# DIY-Arduino-v0_1.net
KiCad netlist of a schematic drawn in EAGLE
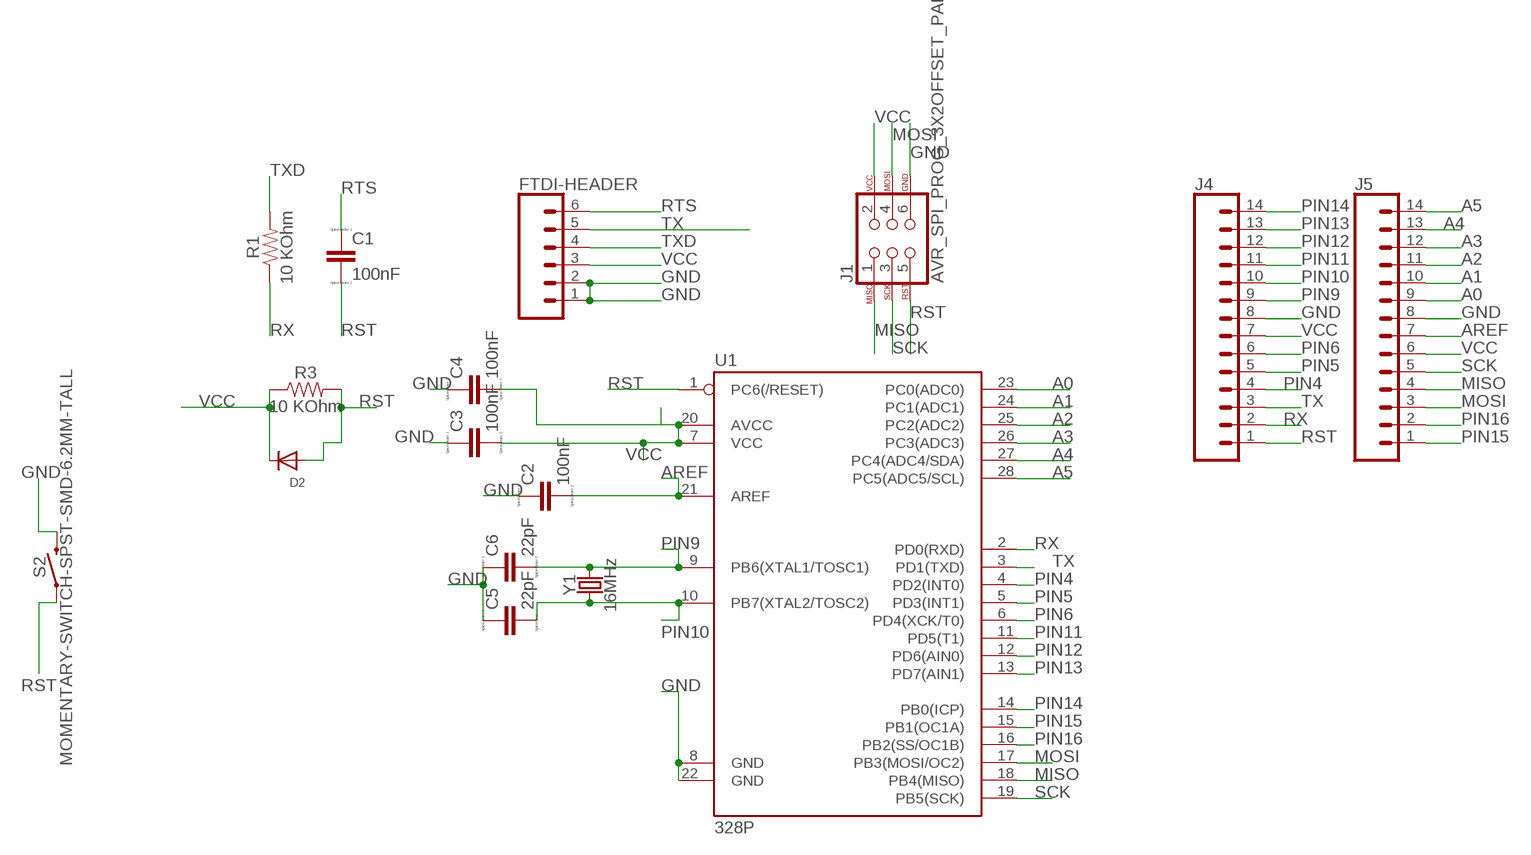
[diagram p0: schematic, sheet 1]

(export (version "E")
  (design (tool "Eeschema 10.0.6"))
  (components
    (comp (ref "C1")
      (value "100nF")
      (footprint "eagle-import:C1206")
      (libsource (lib "eagle-import") (part "CC1206"))
    )
    (comp (ref "C2")
      (value "100nF")
      (footprint "eagle-import:C1206")
      (libsource (lib "eagle-import") (part "CC1206"))
    )
    (comp (ref "C3")
      (value "100nF")
      (footprint "eagle-import:C1206")
      (libsource (lib "eagle-import") (part "CC1206"))
    )
    (comp (ref "C4")
      (value "100nF")
      (footprint "eagle-import:C1206")
      (libsource (lib "eagle-import") (part "CC1206"))
    )
    (comp (ref "C5")
      (value "22pF")
      (footprint "eagle-import:C1206")
      (libsource (lib "eagle-import") (part "CC1206"))
    )
    (comp (ref "C6")
      (value "22pF")
      (footprint "eagle-import:C1206")
      (libsource (lib "eagle-import") (part "CC1206"))
    )
    (comp (ref "D2")
      (value "DIODEDO-1N4148")
      (footprint "eagle-import:DO-1N4148")
      (libsource (lib "eagle-import") (part "DIODEDO-1N4148"))
    )
    (comp (ref "FTDI-HEADER")
      (value "CONN_06NO_SILK_FEMALE_PTH")
      (footprint "eagle-import:1X06_NO_SILK")
      (libsource (lib "eagle-import") (part "CONN_06NO_SILK_FEMALE_PTH"))
    )
    (comp (ref "J1")
      (value "AVR_SPI_PROG_3X2OFFSET_PADS")
      (footprint "eagle-import:2X3_OFFSET")
      (libsource (lib "eagle-import") (part "AVR_SPI_PROG_3X2OFFSET_PADS"))
    )
    (comp (ref "J4")
      (value "CONN_14NO_SILK")
      (footprint "eagle-import:1X14_NO_SILK")
      (libsource (lib "eagle-import") (part "CONN_14NO_SILK"))
    )
    (comp (ref "J5")
      (value "CONN_14NO_SILK")
      (footprint "eagle-import:1X14_NO_SILK")
      (libsource (lib "eagle-import") (part "CONN_14NO_SILK"))
    )
    (comp (ref "R1")
      (value "10 KOhm")
      (footprint "eagle-import:1206")
      (libsource (lib "eagle-import") (part "RESISTOR1206"))
    )
    (comp (ref "R3")
      (value "10 KOhm")
      (footprint "eagle-import:1206")
      (libsource (lib "eagle-import") (part "RESISTOR1206"))
    )
    (comp (ref "S2")
      (value "MOMENTARY-SWITCH-SPST-SMD-6.2MM-TALL")
      (footprint "eagle-import:TACTILE_SWITCH_SMD_6.2MM_TALL")
      (libsource (lib "eagle-import") (part "MOMENTARY-SWITCH-SPST-SMD-6.2MM-TALL"))
    )
    (comp (ref "U1")
      (value "328P")
      (footprint "eagle-import:DIP28")
      (libsource (lib "eagle-import") (part "ATMEGA328P_PDIP"))
    )
    (comp (ref "Y1")
      (value "16MHz")
      (footprint "eagle-import:HC49US")
      (libsource (lib "eagle-import") (part "CRYSTAL-16MHZPTH-HC49US"))
    )
  )
  (nets
    (net (code "1") (name "/A0") (class "Default")
      (node (ref "J5") (pin "9") (pinfunction "9_9") (pintype "passive"))
      (node (ref "U1") (pin "23") (pinfunction "PC0(ADC0)_23") (pintype "bidirectional"))
    )
    (net (code "2") (name "/A1") (class "Default")
      (node (ref "J5") (pin "10") (pinfunction "10_10") (pintype "passive"))
      (node (ref "U1") (pin "24") (pinfunction "PC1(ADC1)_24") (pintype "bidirectional"))
    )
    (net (code "3") (name "/A2") (class "Default")
      (node (ref "J5") (pin "11") (pinfunction "11_11") (pintype "passive"))
      (node (ref "U1") (pin "25") (pinfunction "PC2(ADC2)_25") (pintype "bidirectional"))
    )
    (net (code "4") (name "/A3") (class "Default")
      (node (ref "J5") (pin "12") (pinfunction "12_12") (pintype "passive"))
      (node (ref "U1") (pin "26") (pinfunction "PC3(ADC3)_26") (pintype "bidirectional"))
    )
    (net (code "5") (name "/A4") (class "Default")
      (node (ref "J5") (pin "13") (pinfunction "13_13") (pintype "passive"))
      (node (ref "U1") (pin "27") (pinfunction "PC4(ADC4/SDA)_27") (pintype "bidirectional"))
    )
    (net (code "6") (name "/A5") (class "Default")
      (node (ref "J5") (pin "14") (pinfunction "14_14") (pintype "passive"))
      (node (ref "U1") (pin "28") (pinfunction "PC5(ADC5/SCL)_28") (pintype "bidirectional"))
    )
    (net (code "7") (name "/AREF") (class "Default")
      (node (ref "C2") (pin "2") (pinfunction "2_2") (pintype "passive"))
      (node (ref "J5") (pin "7") (pinfunction "7_7") (pintype "passive"))
      (node (ref "U1") (pin "21") (pinfunction "AREF_21") (pintype "bidirectional"))
    )
    (net (code "8") (name "/GND") (class "Default")
      (node (ref "C2") (pin "1") (pinfunction "1_1") (pintype "passive"))
      (node (ref "C3") (pin "1") (pinfunction "1_1") (pintype "passive"))
      (node (ref "C4") (pin "1") (pinfunction "1_1") (pintype "passive"))
      (node (ref "C5") (pin "1") (pinfunction "1_1") (pintype "passive"))
      (node (ref "C6") (pin "1") (pinfunction "1_1") (pintype "passive"))
      (node (ref "FTDI-HEADER") (pin "1") (pinfunction "1_1") (pintype "passive"))
      (node (ref "FTDI-HEADER") (pin "2") (pinfunction "2_2") (pintype "passive"))
      (node (ref "J1") (pin "6") (pinfunction "6_6") (pintype "passive"))
      (node (ref "J4") (pin "8") (pinfunction "8_8") (pintype "passive"))
      (node (ref "J5") (pin "8") (pinfunction "8_8") (pintype "passive"))
      (node (ref "S2") (pin "B2") (pinfunction "2_B2") (pintype "passive"))
      (node (ref "U1") (pin "22") (pinfunction "GND_22") (pintype "bidirectional"))
      (node (ref "U1") (pin "8") (pinfunction "GND_8") (pintype "bidirectional"))
    )
    (net (code "9") (name "/MISO") (class "Default")
      (node (ref "J1") (pin "1") (pinfunction "1_1") (pintype "passive"))
      (node (ref "J5") (pin "4") (pinfunction "4_4") (pintype "passive"))
      (node (ref "U1") (pin "18") (pinfunction "PB4(MISO)_18") (pintype "bidirectional"))
    )
    (net (code "10") (name "/MOSI") (class "Default")
      (node (ref "J1") (pin "4") (pinfunction "4_4") (pintype "passive"))
      (node (ref "J5") (pin "3") (pinfunction "3_3") (pintype "passive"))
      (node (ref "U1") (pin "17") (pinfunction "PB3(MOSI/OC2)_17") (pintype "bidirectional"))
    )
    (net (code "11") (name "/PIN4") (class "Default")
      (node (ref "J4") (pin "4") (pinfunction "4_4") (pintype "passive"))
      (node (ref "U1") (pin "4") (pinfunction "PD2(INT0)_4") (pintype "bidirectional"))
    )
    (net (code "12") (name "/PIN5") (class "Default")
      (node (ref "J4") (pin "5") (pinfunction "5_5") (pintype "passive"))
      (node (ref "U1") (pin "5") (pinfunction "PD3(INT1)_5") (pintype "bidirectional"))
    )
    (net (code "13") (name "/PIN6") (class "Default")
      (node (ref "J4") (pin "6") (pinfunction "6_6") (pintype "passive"))
      (node (ref "U1") (pin "6") (pinfunction "PD4(XCK/T0)_6") (pintype "bidirectional"))
    )
    (net (code "14") (name "/PIN9") (class "Default")
      (node (ref "C6") (pin "2") (pinfunction "2_2") (pintype "passive"))
      (node (ref "J4") (pin "9") (pinfunction "9_9") (pintype "passive"))
      (node (ref "U1") (pin "9") (pinfunction "PB6(XTAL1/TOSC1)_9") (pintype "bidirectional"))
      (node (ref "Y1") (pin "2") (pinfunction "2_2") (pintype "passive"))
    )
    (net (code "15") (name "/PIN10") (class "Default")
      (node (ref "C5") (pin "2") (pinfunction "2_2") (pintype "passive"))
      (node (ref "J4") (pin "10") (pinfunction "10_10") (pintype "passive"))
      (node (ref "U1") (pin "10") (pinfunction "PB7(XTAL2/TOSC2)_10") (pintype "bidirectional"))
      (node (ref "Y1") (pin "1") (pinfunction "1_1") (pintype "passive"))
    )
    (net (code "16") (name "/PIN11") (class "Default")
      (node (ref "J4") (pin "11") (pinfunction "11_11") (pintype "passive"))
      (node (ref "U1") (pin "11") (pinfunction "PD5(T1)_11") (pintype "bidirectional"))
    )
    (net (code "17") (name "/PIN12") (class "Default")
      (node (ref "J4") (pin "12") (pinfunction "12_12") (pintype "passive"))
      (node (ref "U1") (pin "12") (pinfunction "PD6(AIN0)_12") (pintype "bidirectional"))
    )
    (net (code "18") (name "/PIN13") (class "Default")
      (node (ref "J4") (pin "13") (pinfunction "13_13") (pintype "passive"))
      (node (ref "U1") (pin "13") (pinfunction "PD7(AIN1)_13") (pintype "bidirectional"))
    )
    (net (code "19") (name "/PIN14") (class "Default")
      (node (ref "J4") (pin "14") (pinfunction "14_14") (pintype "passive"))
      (node (ref "U1") (pin "14") (pinfunction "PB0(ICP)_14") (pintype "bidirectional"))
    )
    (net (code "20") (name "/PIN15") (class "Default")
      (node (ref "J5") (pin "1") (pinfunction "1_1") (pintype "passive"))
      (node (ref "U1") (pin "15") (pinfunction "PB1(OC1A)_15") (pintype "bidirectional"))
    )
    (net (code "21") (name "/PIN16") (class "Default")
      (node (ref "J5") (pin "2") (pinfunction "2_2") (pintype "passive"))
      (node (ref "U1") (pin "16") (pinfunction "PB2(SS/OC1B)_16") (pintype "bidirectional"))
    )
    (net (code "22") (name "/RST") (class "Default")
      (node (ref "C1") (pin "2") (pinfunction "2_2") (pintype "passive"))
      (node (ref "D2") (pin "A") (pinfunction "A_A") (pintype "passive"))
      (node (ref "J1") (pin "5") (pinfunction "5_5") (pintype "passive"))
      (node (ref "J4") (pin "1") (pinfunction "1_1") (pintype "passive"))
      (node (ref "R3") (pin "2") (pinfunction "2_2") (pintype "passive"))
      (node (ref "S2") (pin "A2") (pinfunction "1_A2") (pintype "passive"))
      (node (ref "U1") (pin "1") (pinfunction "PC6(/RESET)_1") (pintype "bidirectional"))
    )
    (net (code "23") (name "/RTS") (class "Default")
      (node (ref "C1") (pin "1") (pinfunction "1_1") (pintype "passive"))
      (node (ref "FTDI-HEADER") (pin "6") (pinfunction "6_6") (pintype "passive"))
    )
    (net (code "24") (name "/RX") (class "Default")
      (node (ref "J4") (pin "2") (pinfunction "2_2") (pintype "passive"))
      (node (ref "R1") (pin "1") (pinfunction "1_1") (pintype "passive"))
      (node (ref "U1") (pin "2") (pinfunction "PD0(RXD)_2") (pintype "bidirectional"))
    )
    (net (code "25") (name "/SCK") (class "Default")
      (node (ref "J1") (pin "3") (pinfunction "3_3") (pintype "passive"))
      (node (ref "J5") (pin "5") (pinfunction "5_5") (pintype "passive"))
      (node (ref "U1") (pin "19") (pinfunction "PB5(SCK)_19") (pintype "bidirectional"))
    )
    (net (code "26") (name "/TX") (class "Default")
      (node (ref "FTDI-HEADER") (pin "5") (pinfunction "5_5") (pintype "passive"))
      (node (ref "J4") (pin "3") (pinfunction "3_3") (pintype "passive"))
      (node (ref "U1") (pin "3") (pinfunction "PD1(TXD)_3") (pintype "bidirectional"))
    )
    (net (code "27") (name "/TXD") (class "Default")
      (node (ref "FTDI-HEADER") (pin "4") (pinfunction "4_4") (pintype "passive"))
      (node (ref "R1") (pin "2") (pinfunction "2_2") (pintype "passive"))
    )
    (net (code "28") (name "/VCC") (class "Default")
      (node (ref "C3") (pin "2") (pinfunction "2_2") (pintype "passive"))
      (node (ref "C4") (pin "2") (pinfunction "2_2") (pintype "passive"))
      (node (ref "D2") (pin "C") (pinfunction "C_C") (pintype "passive"))
      (node (ref "FTDI-HEADER") (pin "3") (pinfunction "3_3") (pintype "passive"))
      (node (ref "J1") (pin "2") (pinfunction "2_2") (pintype "passive"))
      (node (ref "J4") (pin "7") (pinfunction "7_7") (pintype "passive"))
      (node (ref "J5") (pin "6") (pinfunction "6_6") (pintype "passive"))
      (node (ref "R3") (pin "1") (pinfunction "1_1") (pintype "passive"))
      (node (ref "U1") (pin "20") (pinfunction "AVCC_20") (pintype "bidirectional"))
      (node (ref "U1") (pin "7") (pinfunction "VCC_7") (pintype "bidirectional"))
    )
  )
)
